# MAGIsCM0Core.net
KiCad netlist of a schematic drawn in Altium Designer
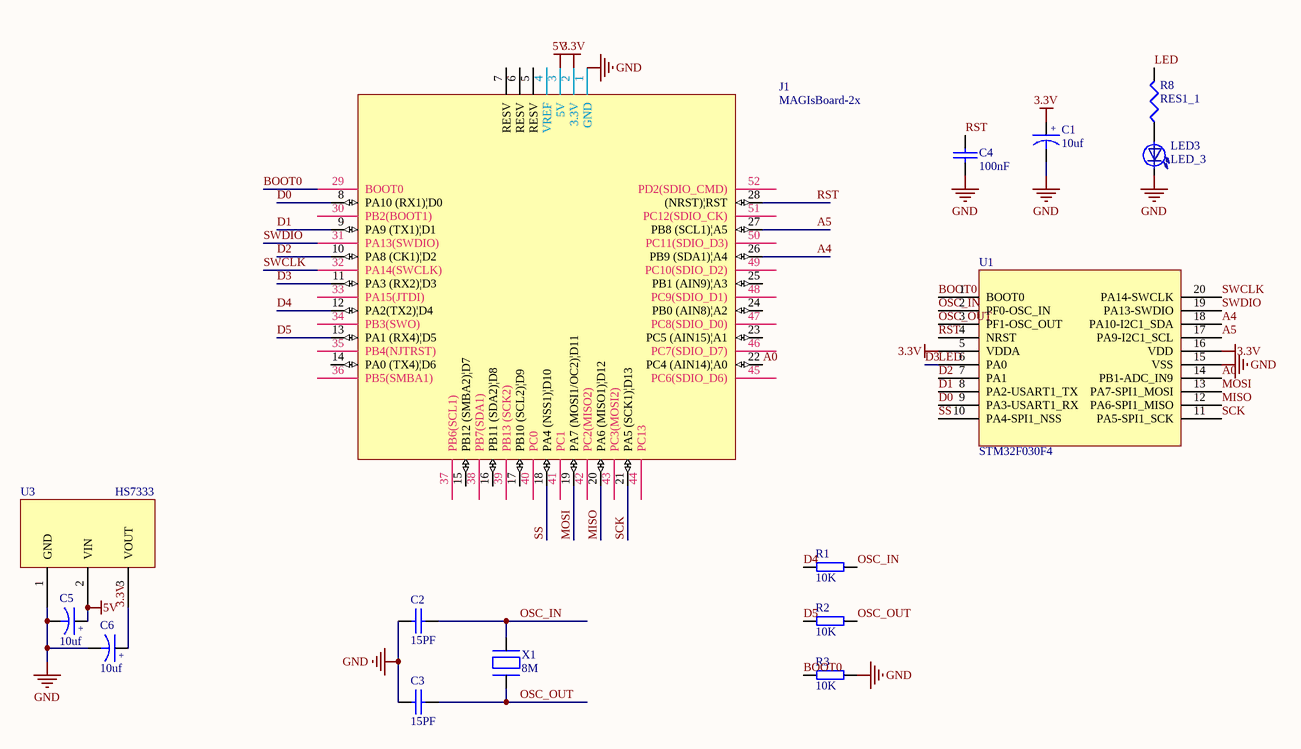
[diagram p0: MAGIsCM0Core.SchDoc]

(export (version "E")
  (design (tool "Eeschema 10.0.6"))
  (components
    (comp (ref "C1")
      (value "10uf")
      (footprint "6-0805_n")
      (description "Capacitor")
      (libsource (lib "电容器") (part "CAPACITOR POL"))
    )
    (comp (ref "C2") (value "15PF") (footprint "6-0805_n") (libsource (lib "STM32") (part "CAP")))
    (comp (ref "C3") (value "15PF") (footprint "6-0805_n") (libsource (lib "STM32") (part "CAP")))
    (comp (ref "C4") (value "100nF") (footprint "6-0805_n") (libsource (lib "STM32") (part "CAP")))
    (comp (ref "C5")
      (value "10uf")
      (footprint "6-0805_n")
      (description "Capacitor")
      (libsource (lib "电容器") (part "CAPACITOR POL"))
    )
    (comp (ref "C6")
      (value "10uf")
      (footprint "6-0805_n")
      (description "Capacitor")
      (libsource (lib "电容器") (part "CAPACITOR POL"))
    )
    (comp (ref "J1")
      (value "MAGIsBoard-2x")
      (footprint "MAGIsBoard-2x")
      (libsource (lib "MAGIsBoard") (part "MAGIsBoard-2x"))
    )
    (comp (ref "LED3") (value "LED_3") (footprint "6-0805_N") (libsource (lib "二极管") (part "LED_3")))
    (comp (ref "R1") (value "10K") (footprint "6-0805_n") (libsource (lib "STM32") (part "RES")))
    (comp (ref "R2") (value "10K") (footprint "6-0805_n") (libsource (lib "STM32") (part "RES")))
    (comp (ref "R3") (value "10K") (footprint "6-0805_n") (libsource (lib "STM32") (part "RES")))
    (comp (ref "R8") (value "RES1_1") (footprint "6-0805_N") (libsource (lib "电阻器") (part "RES1_1")))
    (comp (ref "U1")
      (value "STM32F030F4")
      (footprint "STM32F030")
      (libsource (lib "MCU") (part "STM32F030F4"))
    )
    (comp (ref "U3") (value "HS7333") (footprint "HS7333") (libsource (lib "PMIC") (part "HS7333")))
    (comp (ref "X1") (value "8M") (footprint "5032") (libsource (lib "STM32") (part "CRYSTAL")))
  )
  (nets
    (net (code "1") (name "/A0") (class "Default")
      (node (ref "J1") (pin "22") (pinfunction "PC4_(AIN14)¦A0_22") (pintype "bidirectional"))
      (node (ref "U1") (pin "14") (pinfunction "PB1-ADC_IN9_14") (pintype "passive"))
    )
    (net (code "2") (name "/A4") (class "Default")
      (node (ref "J1") (pin "26") (pinfunction "PB9_(SDA1)¦A4_26") (pintype "bidirectional"))
      (node (ref "U1") (pin "18") (pinfunction "PA10-I2C1_SDA_18") (pintype "passive"))
    )
    (net (code "3") (name "/A5") (class "Default")
      (node (ref "J1") (pin "27") (pinfunction "PB8_(SCL1)¦A5_27") (pintype "bidirectional"))
      (node (ref "U1") (pin "17") (pinfunction "PA9-I2C1_SCL_17") (pintype "passive"))
    )
    (net (code "4") (name "/BOOT0") (class "Default")
      (node (ref "J1") (pin "29") (pinfunction "BOOT0_29") (pintype "passive"))
      (node (ref "R3") (pin "2") (pinfunction "2_2") (pintype "passive"))
      (node (ref "U1") (pin "1") (pinfunction "BOOT0_1") (pintype "passive"))
    )
    (net (code "5") (name "/D0") (class "Default")
      (node (ref "J1") (pin "8") (pinfunction "PA10_(RX1)¦D0_8") (pintype "bidirectional"))
      (node (ref "U1") (pin "9") (pinfunction "PA3-USART1_RX_9") (pintype "passive"))
    )
    (net (code "6") (name "/D1") (class "Default")
      (node (ref "J1") (pin "9") (pinfunction "PA9_(TX1)¦D1_9") (pintype "bidirectional"))
      (node (ref "U1") (pin "8") (pinfunction "PA2-USART1_TX_8") (pintype "passive"))
    )
    (net (code "7") (name "/D2") (class "Default")
      (node (ref "J1") (pin "10") (pinfunction "PA8_(CK1)¦D2_10") (pintype "bidirectional"))
      (node (ref "U1") (pin "7") (pinfunction "PA1_7") (pintype "passive"))
    )
    (net (code "8") (name "/D3") (class "Default")
      (node (ref "J1") (pin "11") (pinfunction "PA3_(RX2)¦D3_11") (pintype "bidirectional"))
      (node (ref "R8") (pin "2") (pinfunction "2_2") (pintype "passive"))
      (node (ref "U1") (pin "6") (pinfunction "PA0_6") (pintype "passive"))
    )
    (net (code "9") (name "/D4") (class "Default")
      (node (ref "J1") (pin "12") (pinfunction "PA2(TX2)¦D4_12") (pintype "bidirectional"))
      (node (ref "R1") (pin "2") (pinfunction "2_2") (pintype "passive"))
    )
    (net (code "10") (name "/D5") (class "Default")
      (node (ref "J1") (pin "13") (pinfunction "PA1_(RX4)¦D5_13") (pintype "bidirectional"))
      (node (ref "R2") (pin "2") (pinfunction "2_2") (pintype "passive"))
    )
    (net (code "11") (name "/MISO") (class "Default")
      (node (ref "J1") (pin "20") (pinfunction "PA6_(MISO1)¦D12_20") (pintype "bidirectional"))
      (node (ref "U1") (pin "12") (pinfunction "PA6-SPI1_MISO_12") (pintype "passive"))
    )
    (net (code "12") (name "/MOSI") (class "Default")
      (node (ref "J1") (pin "19") (pinfunction "PA7_(MOSI1/OC2)¦D11_19") (pintype "bidirectional"))
      (node (ref "U1") (pin "13") (pinfunction "PA7-SPI1_MOSI_13") (pintype "passive"))
    )
    (net (code "13") (name "/OSC_IN") (class "Default")
      (node (ref "C2") (pin "2") (pinfunction "2_2") (pintype "passive"))
      (node (ref "R1") (pin "1") (pinfunction "1_1") (pintype "passive"))
      (node (ref "U1") (pin "2") (pinfunction "PF0-OSC_IN_2") (pintype "passive"))
      (node (ref "X1") (pin "1") (pinfunction "1_1") (pintype "passive"))
    )
    (net (code "14") (name "/OSC_OUT") (class "Default")
      (node (ref "C3") (pin "2") (pinfunction "2_2") (pintype "passive"))
      (node (ref "R2") (pin "1") (pinfunction "1_1") (pintype "passive"))
      (node (ref "U1") (pin "3") (pinfunction "PF1-OSC_OUT_3") (pintype "passive"))
      (node (ref "X1") (pin "2") (pinfunction "2_2") (pintype "passive"))
    )
    (net (code "15") (name "/RST") (class "Default")
      (node (ref "C4") (pin "2") (pinfunction "2_2") (pintype "passive"))
      (node (ref "J1") (pin "28") (pinfunction "(NRST)¦RST_28") (pintype "bidirectional"))
      (node (ref "U1") (pin "4") (pinfunction "NRST_4") (pintype "passive"))
    )
    (net (code "16") (name "/SCK") (class "Default")
      (node (ref "J1") (pin "21") (pinfunction "PA5_(SCK1)¦D13_21") (pintype "bidirectional"))
      (node (ref "U1") (pin "11") (pinfunction "PA5-SPI1_SCK_11") (pintype "passive"))
    )
    (net (code "17") (name "/SS") (class "Default")
      (node (ref "J1") (pin "18") (pinfunction "PA4_(NSS1)¦D10_18") (pintype "bidirectional"))
      (node (ref "U1") (pin "10") (pinfunction "PA4-SPI1_NSS_10") (pintype "passive"))
    )
    (net (code "18") (name "/SWCLK") (class "Default")
      (node (ref "J1") (pin "32") (pinfunction "PA14(SWCLK)_32") (pintype "passive"))
      (node (ref "U1") (pin "20") (pinfunction "PA14-SWCLK_20") (pintype "passive"))
    )
    (net (code "19") (name "/SWDIO") (class "Default")
      (node (ref "J1") (pin "31") (pinfunction "PA13(SWDIO)_31") (pintype "passive"))
      (node (ref "U1") (pin "19") (pinfunction "PA13-SWDIO_19") (pintype "passive"))
    )
    (net (code "20") (name "3.3V") (class "Default")
      (node (ref "C1") (pin "1") (pinfunction "1_1") (pintype "passive"))
      (node (ref "C6") (pin "1") (pinfunction "1_1") (pintype "passive"))
      (node (ref "J1") (pin "2") (pinfunction "3.3V_2") (pintype "power_in"))
      (node (ref "U1") (pin "16") (pinfunction "VDD_16") (pintype "passive"))
      (node (ref "U1") (pin "5") (pinfunction "VDDA_5") (pintype "passive"))
      (node (ref "U3") (pin "3") (pinfunction "VOUT_3") (pintype "passive"))
    )
    (net (code "21") (name "5V") (class "Default")
      (node (ref "C5") (pin "1") (pinfunction "1_1") (pintype "passive"))
      (node (ref "J1") (pin "3") (pinfunction "5V_3") (pintype "power_in"))
      (node (ref "U3") (pin "2") (pinfunction "VIN_2") (pintype "passive"))
    )
    (net (code "22") (name "GND") (class "Default")
      (node (ref "C1") (pin "2") (pinfunction "2_2") (pintype "passive"))
      (node (ref "C2") (pin "1") (pinfunction "1_1") (pintype "passive"))
      (node (ref "C3") (pin "1") (pinfunction "1_1") (pintype "passive"))
      (node (ref "C4") (pin "1") (pinfunction "1_1") (pintype "passive"))
      (node (ref "C5") (pin "2") (pinfunction "2_2") (pintype "passive"))
      (node (ref "C6") (pin "2") (pinfunction "2_2") (pintype "passive"))
      (node (ref "J1") (pin "1") (pinfunction "GND_1") (pintype "power_in"))
      (node (ref "LED3") (pin "2") (pinfunction "K_2") (pintype "passive"))
      (node (ref "R3") (pin "1") (pinfunction "1_1") (pintype "passive"))
      (node (ref "U1") (pin "15") (pinfunction "VSS_15") (pintype "passive"))
      (node (ref "U3") (pin "1") (pinfunction "GND_1") (pintype "passive"))
    )
    (net (code "23") (name "Net-(LED3-A)") (class "Default")
      (node (ref "LED3") (pin "1") (pinfunction "A_1") (pintype "passive"))
      (node (ref "R8") (pin "1") (pinfunction "1_1") (pintype "passive"))
    )
    (net (code "24") (name "unconnected-(J1-PA0_(TX4)¦D6-Pad14)") (class "Default")
      (node (ref "J1") (pin "14") (pinfunction "PA0_(TX4)¦D6_14") (pintype "bidirectional"))
    )
    (net (code "25") (name "unconnected-(J1-PA15(JTDI)-Pad33)") (class "Default")
      (node (ref "J1") (pin "33") (pinfunction "PA15(JTDI)_33") (pintype "passive"))
    )
    (net (code "26") (name "unconnected-(J1-PB0_(AIN8)¦A2-Pad24)") (class "Default")
      (node (ref "J1") (pin "24") (pinfunction "PB0_(AIN8)¦A2_24") (pintype "bidirectional"))
    )
    (net (code "27") (name "unconnected-(J1-PB1_(AIN9)¦A3-Pad25)") (class "Default")
      (node (ref "J1") (pin "25") (pinfunction "PB1_(AIN9)¦A3_25") (pintype "bidirectional"))
    )
    (net (code "28") (name "unconnected-(J1-PB2(BOOT1)-Pad30)") (class "Default")
      (node (ref "J1") (pin "30") (pinfunction "PB2(BOOT1)_30") (pintype "passive"))
    )
    (net (code "29") (name "unconnected-(J1-PB3(SWO)-Pad34)") (class "Default")
      (node (ref "J1") (pin "34") (pinfunction "PB3(SWO)_34") (pintype "passive"))
    )
    (net (code "30") (name "unconnected-(J1-PB4(NJTRST)-Pad35)") (class "Default")
      (node (ref "J1") (pin "35") (pinfunction "PB4(NJTRST)_35") (pintype "passive"))
    )
    (net (code "31") (name "unconnected-(J1-PB5(SMBA1)-Pad36)") (class "Default")
      (node (ref "J1") (pin "36") (pinfunction "PB5(SMBA1)_36") (pintype "passive"))
    )
    (net (code "32") (name "unconnected-(J1-PB6(SCL1)-Pad37)") (class "Default")
      (node (ref "J1") (pin "37") (pinfunction "PB6(SCL1)_37") (pintype "passive"))
    )
    (net (code "33") (name "unconnected-(J1-PB7(SDA1)-Pad38)") (class "Default")
      (node (ref "J1") (pin "38") (pinfunction "PB7(SDA1)_38") (pintype "passive"))
    )
    (net (code "34") (name "unconnected-(J1-PB10_(SCL2)¦D9-Pad17)") (class "Default")
      (node (ref "J1") (pin "17") (pinfunction "PB10_(SCL2)¦D9_17") (pintype "bidirectional"))
    )
    (net (code "35") (name "unconnected-(J1-PB11_(SDA2)¦D8-Pad16)") (class "Default")
      (node (ref "J1") (pin "16") (pinfunction "PB11_(SDA2)¦D8_16") (pintype "bidirectional"))
    )
    (net (code "36") (name "unconnected-(J1-PB12_(SMBA2)¦D7-Pad15)") (class "Default")
      (node (ref "J1") (pin "15") (pinfunction "PB12_(SMBA2)¦D7_15") (pintype "bidirectional"))
    )
    (net (code "37") (name "unconnected-(J1-PB13_(SCK2)-Pad39)") (class "Default")
      (node (ref "J1") (pin "39") (pinfunction "PB13_(SCK2)_39") (pintype "passive"))
    )
    (net (code "38") (name "unconnected-(J1-PC0-Pad40)") (class "Default")
      (node (ref "J1") (pin "40") (pinfunction "PC0_40") (pintype "passive"))
    )
    (net (code "39") (name "unconnected-(J1-PC1-Pad41)") (class "Default")
      (node (ref "J1") (pin "41") (pinfunction "PC1_41") (pintype "passive"))
    )
    (net (code "40") (name "unconnected-(J1-PC2(MISO2)-Pad42)") (class "Default")
      (node (ref "J1") (pin "42") (pinfunction "PC2(MISO2)_42") (pintype "passive"))
    )
    (net (code "41") (name "unconnected-(J1-PC3(MOSI2)-Pad43)") (class "Default")
      (node (ref "J1") (pin "43") (pinfunction "PC3(MOSI2)_43") (pintype "passive"))
    )
    (net (code "42") (name "unconnected-(J1-PC5_(AIN15)¦A1-Pad23)") (class "Default")
      (node (ref "J1") (pin "23") (pinfunction "PC5_(AIN15)¦A1_23") (pintype "bidirectional"))
    )
    (net (code "43") (name "unconnected-(J1-PC6(SDIO_D6)-Pad45)") (class "Default")
      (node (ref "J1") (pin "45") (pinfunction "PC6(SDIO_D6)_45") (pintype "passive"))
    )
    (net (code "44") (name "unconnected-(J1-PC7(SDIO_D7)-Pad46)") (class "Default")
      (node (ref "J1") (pin "46") (pinfunction "PC7(SDIO_D7)_46") (pintype "passive"))
    )
    (net (code "45") (name "unconnected-(J1-PC8(SDIO_D0)-Pad47)") (class "Default")
      (node (ref "J1") (pin "47") (pinfunction "PC8(SDIO_D0)_47") (pintype "passive"))
    )
    (net (code "46") (name "unconnected-(J1-PC9(SDIO_D1)-Pad48)") (class "Default")
      (node (ref "J1") (pin "48") (pinfunction "PC9(SDIO_D1)_48") (pintype "passive"))
    )
    (net (code "47") (name "unconnected-(J1-PC10(SDIO_D2)-Pad49)") (class "Default")
      (node (ref "J1") (pin "49") (pinfunction "PC10(SDIO_D2)_49") (pintype "passive"))
    )
    (net (code "48") (name "unconnected-(J1-PC11(SDIO_D3)-Pad50)") (class "Default")
      (node (ref "J1") (pin "50") (pinfunction "PC11(SDIO_D3)_50") (pintype "passive"))
    )
    (net (code "49") (name "unconnected-(J1-PC12(SDIO_CK)-Pad51)") (class "Default")
      (node (ref "J1") (pin "51") (pinfunction "PC12(SDIO_CK)_51") (pintype "passive"))
    )
    (net (code "50") (name "unconnected-(J1-PC13-Pad44)") (class "Default")
      (node (ref "J1") (pin "44") (pinfunction "PC13_44") (pintype "passive"))
    )
    (net (code "51") (name "unconnected-(J1-PD2(SDIO_CMD)-Pad52)") (class "Default")
      (node (ref "J1") (pin "52") (pinfunction "PD2(SDIO_CMD)_52") (pintype "passive"))
    )
    (net (code "52") (name "unconnected-(J1-RESV-Pad5)") (class "Default")
      (node (ref "J1") (pin "5") (pinfunction "RESV_5") (pintype "passive"))
    )
    (net (code "53") (name "unconnected-(J1-RESV-Pad6)") (class "Default")
      (node (ref "J1") (pin "6") (pinfunction "RESV_6") (pintype "passive"))
    )
    (net (code "54") (name "unconnected-(J1-RESV-Pad7)") (class "Default")
      (node (ref "J1") (pin "7") (pinfunction "RESV_7") (pintype "passive"))
    )
    (net (code "55") (name "unconnected-(J1-VREF-Pad4)") (class "Default")
      (node (ref "J1") (pin "4") (pinfunction "VREF_4") (pintype "passive"))
    )
  )
)
